# Analog_Light_Project_Adjusted_Schematic.net
KiCad netlist of a schematic drawn in EAGLE
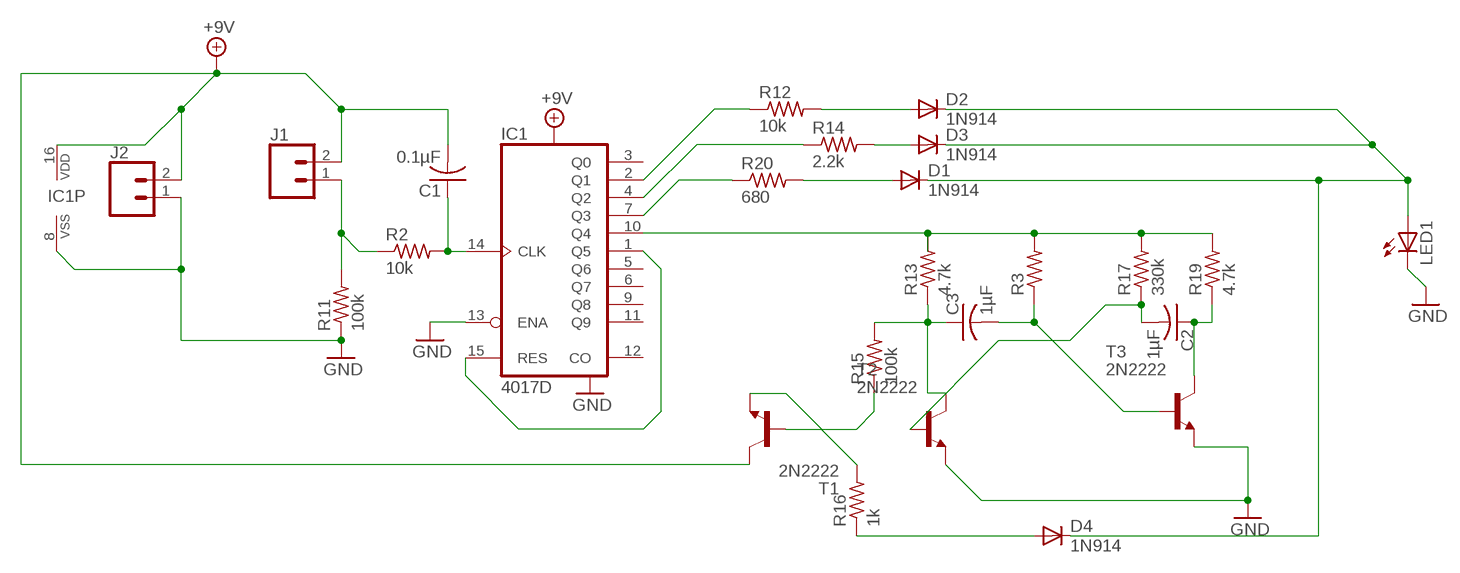
[diagram p0: schematic, sheet 1]

(export (version "E")
  (design (tool "Eeschema 10.0.6"))
  (components
    (comp (ref "C1")
      (value "0.1µF")
      (footprint "eagle-import:C025-024X044")
      (libsource (lib "eagle-import") (part "rcl_334_C-US025-024X044"))
    )
    (comp (ref "C2")
      (value "1µF")
      (footprint "eagle-import:C0805")
      (libsource (lib "eagle-import") (part "C-USC0805"))
    )
    (comp (ref "C3")
      (value "1µF")
      (footprint "eagle-import:C025-024X044")
      (libsource (lib "eagle-import") (part "rcl_334_C-US025-024X044"))
    )
    (comp (ref "D1")
      (value "1N914")
      (footprint "eagle-import:DO41-10")
      (libsource (lib "eagle-import") (part "1N4004"))
    )
    (comp (ref "D2")
      (value "1N914")
      (footprint "eagle-import:DO41-10")
      (libsource (lib "eagle-import") (part "1N4004"))
    )
    (comp (ref "D3")
      (value "1N914")
      (footprint "eagle-import:DO41-10")
      (libsource (lib "eagle-import") (part "1N4004"))
    )
    (comp (ref "D4")
      (value "1N914")
      (footprint "eagle-import:DO41-10")
      (libsource (lib "eagle-import") (part "1N4004"))
    )
    (comp (ref "IC1")
      (value "4017D")
      (footprint "eagle-import:SO16")
      (libsource (lib "eagle-import") (part "4017D"))
    )
    (comp (ref "J1")
      (value "CONN_02")
      (footprint "eagle-import:1X02")
      (libsource (lib "eagle-import") (part "CONN_02"))
    )
    (comp (ref "J2")
      (value "CONN_02")
      (footprint "eagle-import:1X02")
      (libsource (lib "eagle-import") (part "CONN_02"))
    )
    (comp (ref "LED1")
      (value "LED5MM")
      (footprint "eagle-import:LED5MM")
      (libsource (lib "eagle-import") (part "LED5MM"))
    )
    (comp (ref "R2")
      (value "10k")
      (footprint "eagle-import:0204_5")
      (libsource (lib "eagle-import") (part "rcl_334_R-US_0204/5"))
    )
    (comp (ref "R3")
      (value "R-US_0204/5")
      (footprint "eagle-import:0204_5")
      (libsource (lib "eagle-import") (part "rcl_334_R-US_0204/5"))
    )
    (comp (ref "R11")
      (value "100k")
      (footprint "eagle-import:M0805")
      (libsource (lib "eagle-import") (part "R-US_M0805"))
    )
    (comp (ref "R12")
      (value "10k")
      (footprint "eagle-import:M0805")
      (libsource (lib "eagle-import") (part "R-US_M0805"))
    )
    (comp (ref "R13")
      (value "4.7k")
      (footprint "eagle-import:M0805")
      (libsource (lib "eagle-import") (part "R-US_M0805"))
    )
    (comp (ref "R14")
      (value "2.2k")
      (footprint "eagle-import:M0805")
      (libsource (lib "eagle-import") (part "R-US_M0805"))
    )
    (comp (ref "R15")
      (value "100k")
      (footprint "eagle-import:M0805")
      (libsource (lib "eagle-import") (part "R-US_M0805"))
    )
    (comp (ref "R16")
      (value "1k")
      (footprint "eagle-import:M0805")
      (libsource (lib "eagle-import") (part "R-US_M0805"))
    )
    (comp (ref "R17")
      (value "330k")
      (footprint "eagle-import:M0805")
      (libsource (lib "eagle-import") (part "R-US_M0805"))
    )
    (comp (ref "R19")
      (value "4.7k")
      (footprint "eagle-import:M0805")
      (libsource (lib "eagle-import") (part "R-US_M0805"))
    )
    (comp (ref "R20")
      (value "680")
      (footprint "eagle-import:M0805")
      (libsource (lib "eagle-import") (part "R-US_M0805"))
    )
    (comp (ref "T1")
      (value "2N2222")
      (footprint "eagle-import:TO92-EBC-OVAL")
      (libsource (lib "eagle-import") (part "2N2222"))
    )
    (comp (ref "T2")
      (value "2N2222")
      (footprint "eagle-import:TO92-EBC-OVAL")
      (libsource (lib "eagle-import") (part "2N2222"))
    )
    (comp (ref "T3")
      (value "2N2222")
      (footprint "eagle-import:TO92-EBC-OVAL")
      (libsource (lib "eagle-import") (part "2N2222"))
    )
  )
  (nets
    (net (code "1") (name "+9V") (class "Default")
      (node (ref "C1") (pin "2") (pinfunction "2_2") (pintype "passive"))
      (node (ref "IC1") (pin "16") (pinfunction "VDD_16") (pintype "power_in"))
      (node (ref "J1") (pin "2") (pinfunction "2_2") (pintype "passive"))
      (node (ref "J2") (pin "2") (pinfunction "2_2") (pintype "passive"))
      (node (ref "T1") (pin "C") (pinfunction "C_C") (pintype "passive"))
    )
    (net (code "2") (name "GND") (class "Default")
      (node (ref "IC1") (pin "13") (pinfunction "ENA_13") (pintype "input"))
      (node (ref "IC1") (pin "8") (pinfunction "VSS_8") (pintype "power_in"))
      (node (ref "J2") (pin "1") (pinfunction "1_1") (pintype "passive"))
      (node (ref "LED1") (pin "K") (pinfunction "C_K") (pintype "passive"))
      (node (ref "R11") (pin "1") (pinfunction "1_1") (pintype "passive"))
      (node (ref "T2") (pin "E") (pinfunction "E_E") (pintype "passive"))
      (node (ref "T3") (pin "E") (pinfunction "E_E") (pintype "passive"))
    )
    (net (code "3") (name "Net-(C2-Pad1)") (class "Default")
      (node (ref "C2") (pin "1") (pinfunction "1_1") (pintype "passive"))
      (node (ref "R19") (pin "1") (pinfunction "1_1") (pintype "passive"))
      (node (ref "T3") (pin "C") (pinfunction "C_C") (pintype "passive"))
    )
    (net (code "4") (name "Net-(C2-Pad2)") (class "Default")
      (node (ref "C2") (pin "2") (pinfunction "2_2") (pintype "passive"))
      (node (ref "R17") (pin "1") (pinfunction "1_1") (pintype "passive"))
      (node (ref "T2") (pin "B") (pinfunction "B_B") (pintype "passive"))
    )
    (net (code "5") (name "Net-(C3-Pad1)") (class "Default")
      (node (ref "C3") (pin "1") (pinfunction "1_1") (pintype "passive"))
      (node (ref "R13") (pin "1") (pinfunction "1_1") (pintype "passive"))
      (node (ref "R15") (pin "2") (pinfunction "2_2") (pintype "passive"))
      (node (ref "T2") (pin "C") (pinfunction "C_C") (pintype "passive"))
    )
    (net (code "6") (name "Net-(C3-Pad2)") (class "Default")
      (node (ref "C3") (pin "2") (pinfunction "2_2") (pintype "passive"))
      (node (ref "R3") (pin "1") (pinfunction "1_1") (pintype "passive"))
      (node (ref "T3") (pin "B") (pinfunction "B_B") (pintype "passive"))
    )
    (net (code "7") (name "Net-(D1-PadA)") (class "Default")
      (node (ref "D1") (pin "A") (pinfunction "A_A") (pintype "passive"))
      (node (ref "R20") (pin "2") (pinfunction "2_2") (pintype "passive"))
    )
    (net (code "8") (name "Net-(D1-PadC)") (class "Default")
      (node (ref "D1") (pin "C") (pinfunction "C_C") (pintype "passive"))
      (node (ref "D2") (pin "C") (pinfunction "C_C") (pintype "passive"))
      (node (ref "D3") (pin "C") (pinfunction "C_C") (pintype "passive"))
      (node (ref "D4") (pin "C") (pinfunction "C_C") (pintype "passive"))
      (node (ref "LED1") (pin "A") (pinfunction "A_A") (pintype "passive"))
    )
    (net (code "9") (name "Net-(D2-PadA)") (class "Default")
      (node (ref "D2") (pin "A") (pinfunction "A_A") (pintype "passive"))
      (node (ref "R12") (pin "2") (pinfunction "2_2") (pintype "passive"))
    )
    (net (code "10") (name "Net-(D3-PadA)") (class "Default")
      (node (ref "D3") (pin "A") (pinfunction "A_A") (pintype "passive"))
      (node (ref "R14") (pin "2") (pinfunction "2_2") (pintype "passive"))
    )
    (net (code "11") (name "Net-(D4-PadA)") (class "Default")
      (node (ref "D4") (pin "A") (pinfunction "A_A") (pintype "passive"))
      (node (ref "R16") (pin "1") (pinfunction "1_1") (pintype "passive"))
    )
    (net (code "12") (name "Net-(IC1A-CLK)") (class "Default")
      (node (ref "C1") (pin "1") (pinfunction "1_1") (pintype "passive"))
      (node (ref "IC1") (pin "14") (pinfunction "CLK_14") (pintype "input"))
      (node (ref "R2") (pin "2") (pinfunction "2_2") (pintype "passive"))
    )
    (net (code "13") (name "Net-(IC1A-Q1)") (class "Default")
      (node (ref "IC1") (pin "2") (pinfunction "Q1_2") (pintype "output"))
      (node (ref "R12") (pin "1") (pinfunction "1_1") (pintype "passive"))
    )
    (net (code "14") (name "Net-(IC1A-Q2)") (class "Default")
      (node (ref "IC1") (pin "4") (pinfunction "Q2_4") (pintype "output"))
      (node (ref "R14") (pin "1") (pinfunction "1_1") (pintype "passive"))
    )
    (net (code "15") (name "Net-(IC1A-Q3)") (class "Default")
      (node (ref "IC1") (pin "7") (pinfunction "Q3_7") (pintype "output"))
      (node (ref "R20") (pin "1") (pinfunction "1_1") (pintype "passive"))
    )
    (net (code "16") (name "Net-(IC1A-Q4)") (class "Default")
      (node (ref "IC1") (pin "10") (pinfunction "Q4_10") (pintype "output"))
      (node (ref "R13") (pin "2") (pinfunction "2_2") (pintype "passive"))
      (node (ref "R17") (pin "2") (pinfunction "2_2") (pintype "passive"))
      (node (ref "R19") (pin "2") (pinfunction "2_2") (pintype "passive"))
      (node (ref "R3") (pin "2") (pinfunction "2_2") (pintype "passive"))
    )
    (net (code "17") (name "Net-(IC1A-Q5)") (class "Default")
      (node (ref "IC1") (pin "1") (pinfunction "Q5_1") (pintype "output"))
      (node (ref "IC1") (pin "15") (pinfunction "RES_15") (pintype "input"))
    )
    (net (code "18") (name "Net-(J1-Pad1)") (class "Default")
      (node (ref "J1") (pin "1") (pinfunction "1_1") (pintype "passive"))
      (node (ref "R11") (pin "2") (pinfunction "2_2") (pintype "passive"))
      (node (ref "R2") (pin "1") (pinfunction "1_1") (pintype "passive"))
    )
    (net (code "19") (name "Net-(R15-Pad1)") (class "Default")
      (node (ref "R15") (pin "1") (pinfunction "1_1") (pintype "passive"))
      (node (ref "T1") (pin "B") (pinfunction "B_B") (pintype "passive"))
    )
    (net (code "20") (name "Net-(R16-Pad2)") (class "Default")
      (node (ref "R16") (pin "2") (pinfunction "2_2") (pintype "passive"))
      (node (ref "T1") (pin "E") (pinfunction "E_E") (pintype "passive"))
    )
    (net (code "21") (name "unconnected-(IC1A-CO-Pad12)") (class "Default")
      (node (ref "IC1") (pin "12") (pinfunction "CO_12") (pintype "output"))
    )
    (net (code "22") (name "unconnected-(IC1A-Q0-Pad3)") (class "Default")
      (node (ref "IC1") (pin "3") (pinfunction "Q0_3") (pintype "output"))
    )
    (net (code "23") (name "unconnected-(IC1A-Q6-Pad5)") (class "Default")
      (node (ref "IC1") (pin "5") (pinfunction "Q6_5") (pintype "output"))
    )
    (net (code "24") (name "unconnected-(IC1A-Q7-Pad6)") (class "Default")
      (node (ref "IC1") (pin "6") (pinfunction "Q7_6") (pintype "output"))
    )
    (net (code "25") (name "unconnected-(IC1A-Q8-Pad9)") (class "Default")
      (node (ref "IC1") (pin "9") (pinfunction "Q8_9") (pintype "output"))
    )
    (net (code "26") (name "unconnected-(IC1A-Q9-Pad11)") (class "Default")
      (node (ref "IC1") (pin "11") (pinfunction "Q9_11") (pintype "output"))
    )
  )
)
